# Power_Supply.net
KiCad netlist of a schematic drawn in Altium Designer
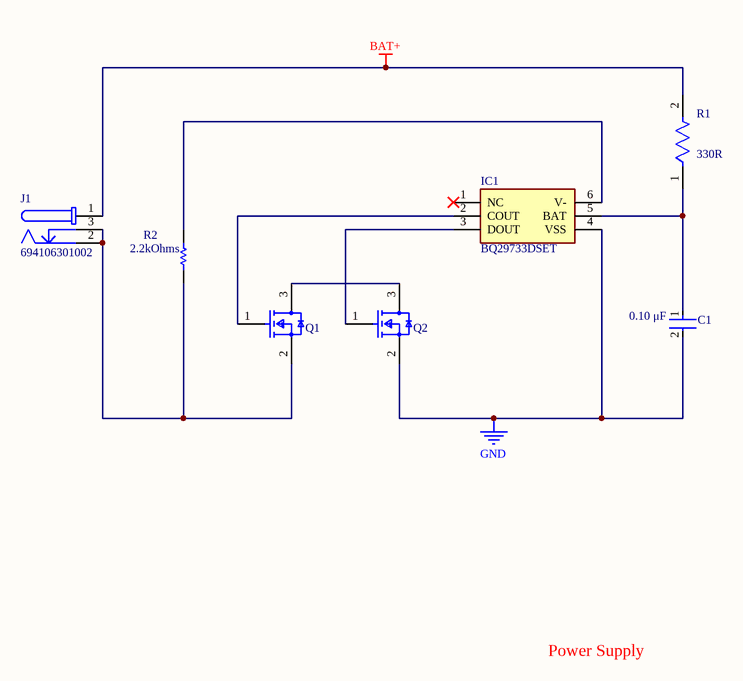
[diagram p0: Power_Supply.SchDoc]

(export (version "E")
  (design (tool "Eeschema 10.0.6"))
  (components
    (comp (ref "C1")
      (value "C0603C104K5RACTU")
      (footprint "FP-C0603C-CF-MFG")
      (description "CAP CER 0.1UF 50V X7R 0603")
      (fields
        (field (name "TOLERANCE") "0.1")
        (field (name "MANUFACTURER") "KEMET")
        (field (name "CAPACITANCE") "0.10 μF")
      )
      (libsource (lib "Altium Content Vault") (part "b4654b650e69147ec39a6b967a45e02"))
    )
    (comp (ref "IC1")
      (value "BQ29733DSET")
      (footprint "SamacSys:SON50P150X150X80-6N")
      (description "Power Supply Support Circuit, Fixed, 1 Channel, PDSO6")
      (fields
        (field (name "MOUSER PART NUMBER") "595-BQ29733DSET")
        (field (name "MANUFACTURER") "Texas Instruments")
      )
      (libsource (lib "*") (part "BQ29733DSET"))
    )
    (comp (ref "J1")
      (value "694106301002")
      (footprint "694106301002")
      (fields (field (name "MANUFACTURER") "Wurth Electronics"))
      (libsource (lib "Altium Content Vault") (part "DC Power Jack"))
    )
    (comp (ref "Q1")
      (value "2N7002-7-F")
      (footprint "FP-SOT23-MFG")
      (description "MOSFET N-CH 60V 115MA SOT23-3")
      (fields (field (name "VOLTAGE") "60V") (field (name "MANUFACTURER") "Diodes"))
      (libsource (lib "Altium Content Vault") (part "3b9c635fedb024a5347a57b145af9cc"))
    )
    (comp (ref "Q2")
      (value "2N7002-7-F")
      (footprint "FP-SOT23-MFG")
      (description "MOSFET N-CH 60V 115MA SOT23-3")
      (fields (field (name "VOLTAGE") "60V") (field (name "MANUFACTURER") "Diodes"))
      (libsource (lib "Altium Content Vault") (part "3b9c635fedb024a5347a57b145af9cc"))
    )
    (comp (ref "R1")
      (value "330R")
      (footprint "FP-ERA3A-MFG")
      (fields
        (field (name "TOLERANCE") "0.1%")
        (field (name "MANUFACTURER") "Panasonic")
        (field (name "MANUFACTURER PART NUMBER") "ERA-3AEB331V")
      )
      (libsource (lib "Altium Content Vault") (part "8db39607336c341a927600551d01821"))
    )
    (comp (ref "R2")
      (value "RC0603FR-072K2L")
      (footprint "RESC1608X55X25LL10T15")
      (fields
        (field (name "TOLERANCE") "1%")
        (field (name "RESISTANCE") "2.2kOhms")
        (field (name "MANUFACTURER") "Yageo")
        (field (name "POWER") "100mW")
      )
      (libsource (lib "Altium Content Vault") (part "RES-2"))
    )
  )
  (nets
    (net (code "1") (name "BAT+") (class "Default")
      (node (ref "J1") (pin "1") (pinfunction "1_1") (pintype "passive"))
      (node (ref "R1") (pin "2") (pinfunction "2_2") (pintype "passive"))
    )
    (net (code "2") (name "GND") (class "Default")
      (node (ref "C1") (pin "2") (pinfunction "2_2") (pintype "passive"))
      (node (ref "IC1") (pin "4") (pinfunction "VSS_4") (pintype "passive"))
      (node (ref "Q2") (pin "2") (pinfunction "S_2") (pintype "passive"))
    )
    (net (code "3") (name "Net-(IC1-BAT)") (class "Default")
      (node (ref "C1") (pin "1") (pinfunction "1_1") (pintype "passive"))
      (node (ref "IC1") (pin "5") (pinfunction "BAT_5") (pintype "passive"))
      (node (ref "R1") (pin "1") (pinfunction "1_1") (pintype "passive"))
    )
    (net (code "4") (name "Net-(IC1-COUT)") (class "Default")
      (node (ref "IC1") (pin "2") (pinfunction "COUT_2") (pintype "passive"))
      (node (ref "Q1") (pin "1") (pinfunction "G_1") (pintype "passive"))
    )
    (net (code "5") (name "Net-(IC1-DOUT)") (class "Default")
      (node (ref "IC1") (pin "3") (pinfunction "DOUT_3") (pintype "passive"))
      (node (ref "Q2") (pin "1") (pinfunction "G_1") (pintype "passive"))
    )
    (net (code "6") (name "Net-(IC1-V-)") (class "Default")
      (node (ref "IC1") (pin "6") (pinfunction "V-_6") (pintype "passive"))
      (node (ref "R2") (pin "2") (pinfunction "2_2") (pintype "passive"))
    )
    (net (code "7") (name "Net-(Q1-D)") (class "Default")
      (node (ref "Q1") (pin "3") (pinfunction "D_3") (pintype "passive"))
      (node (ref "Q2") (pin "3") (pinfunction "D_3") (pintype "passive"))
    )
    (net (code "8") (name "Net-(Q1-S)") (class "Default")
      (node (ref "J1") (pin "2") (pinfunction "2_2") (pintype "passive"))
      (node (ref "J1") (pin "3") (pinfunction "3_3") (pintype "passive"))
      (node (ref "Q1") (pin "2") (pinfunction "S_2") (pintype "passive"))
      (node (ref "R2") (pin "1") (pinfunction "1_1") (pintype "passive"))
    )
    (net (code "9") (name "unconnected-(IC1-NC-Pad1)") (class "Default")
      (node (ref "IC1") (pin "1") (pinfunction "NC_1") (pintype "passive+no_connect"))
    )
  )
)
